# J2.net
KiCad netlist of a schematic drawn in Altium Designer
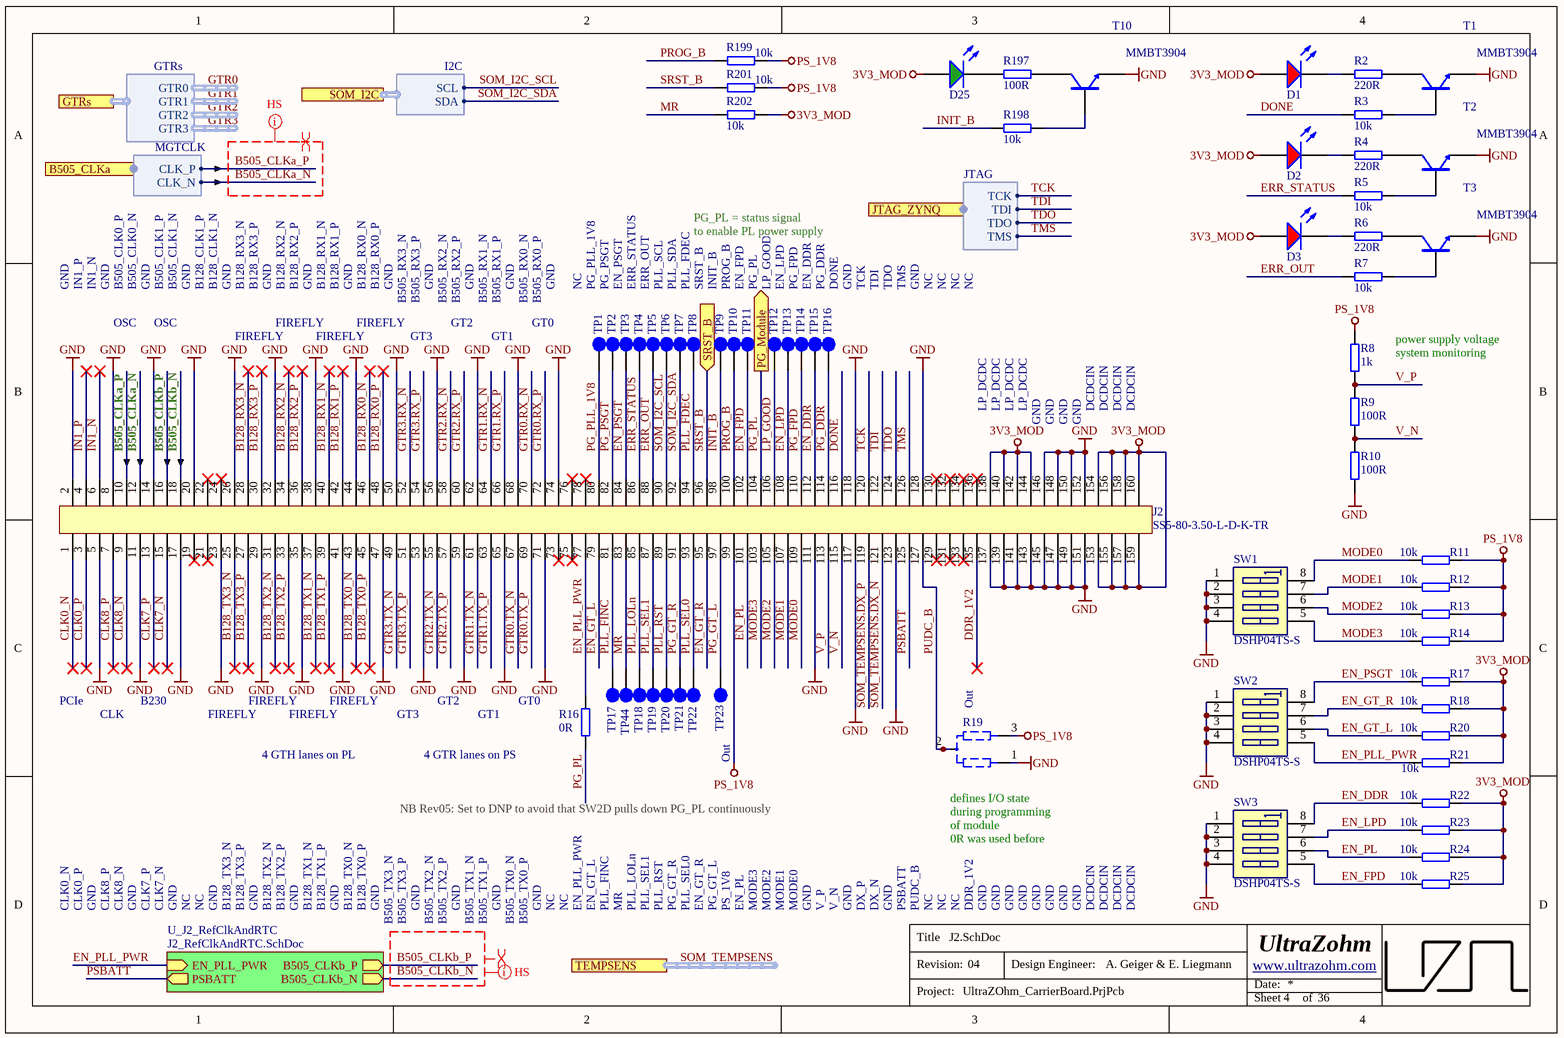
[diagram p0: J2.SchDoc]

(export (version "E")
  (design (tool "Eeschema 10.0.6"))
  (components
    (comp (ref "D1")
      (value "LED Red")
      (footprint "WL-SMCW_0603")
      (description "Standard LEDs - SMD 0603 red")
      (fields
        (field (name "MANUFACTURER PART NUMBER") "UZgen_LED_0603_Red")
        (field (name "MANUFACTURER") "UZgen")
        (field (name "CREATED FROM") "UZgenTool")
      )
      (libsource (lib "user") (part "LED_Red"))
    )
    (comp (ref "D2")
      (value "LED Red")
      (footprint "WL-SMCW_0603")
      (description "Standard LEDs - SMD 0603 red")
      (fields
        (field (name "MANUFACTURER PART NUMBER") "UZgen_LED_0603_Red")
        (field (name "MANUFACTURER") "UZgen")
        (field (name "CREATED FROM") "UZgenTool")
      )
      (libsource (lib "user") (part "LED_Red"))
    )
    (comp (ref "D3")
      (value "LED Red")
      (footprint "WL-SMCW_0603")
      (description "Standard LEDs - SMD 0603 red")
      (fields
        (field (name "MANUFACTURER PART NUMBER") "UZgen_LED_0603_Red")
        (field (name "MANUFACTURER") "UZgen")
        (field (name "CREATED FROM") "UZgenTool")
      )
      (libsource (lib "user") (part "LED_Red"))
    )
    (comp (ref "D25")
      (value "LED Green")
      (footprint "WL-SMCW_0603")
      (description "Standard LEDs - SMD 0603 green")
      (fields
        (field (name "MANUFACTURER PART NUMBER") "UZgen_LED_0603_Green")
        (field (name "MANUFACTURER") "UZgen")
        (field (name "CREATED FROM") "UZgenTool")
      )
      (libsource (lib "user") (part "LED_Green"))
    )
    (comp (ref "J2")
      (value "SS5-80-3.50-L-D-K-TR")
      (footprint "SS5-80-3.50-L-D-K-TR")
      (description "0.5 mm Ultra Fine Pitch Socket REF192552-01, 160 Pins")
      (fields
        (field (name "MANUFACTURER") "SAMTEC")
        (field (name "LCSC PART NUMBER") "C5292077")
        (field (name "CREATED FROM") "MGremer")
      )
      (libsource (lib "user") (part "SS5-80-3.50-L-D-K-TR"))
    )
    (comp (ref "R2")
      (value "220R")
      (footprint "R_0603_TE")
      (description "Generic resistor")
      (fields
        (field (name "TOLERANCE") "1 %")
        (field (name "MANUFACTURER PART NUMBER") "UZgen_R_0603_220R")
        (field (name "CREATED FROM") "UZgenTool")
      )
      (libsource (lib "user") (part "RES"))
    )
    (comp (ref "R3")
      (value "10k")
      (footprint "R_0603_TE")
      (description "Generic resistor")
      (fields
        (field (name "TOLERANCE") "1 %")
        (field (name "MANUFACTURER PART NUMBER") "UZgen_R_0603_10k")
        (field (name "CREATED FROM") "AGeiger")
      )
      (libsource (lib "user") (part "RES"))
    )
    (comp (ref "R4")
      (value "220R")
      (footprint "R_0603_TE")
      (description "Generic resistor")
      (fields
        (field (name "TOLERANCE") "1 %")
        (field (name "MANUFACTURER PART NUMBER") "UZgen_R_0603_220R")
        (field (name "CREATED FROM") "UZgenTool")
      )
      (libsource (lib "user") (part "RES"))
    )
    (comp (ref "R5")
      (value "10k")
      (footprint "R_0603_TE")
      (description "Generic resistor")
      (fields
        (field (name "TOLERANCE") "1 %")
        (field (name "MANUFACTURER PART NUMBER") "UZgen_R_0603_10k")
        (field (name "CREATED FROM") "AGeiger")
      )
      (libsource (lib "user") (part "RES"))
    )
    (comp (ref "R6")
      (value "220R")
      (footprint "R_0603_TE")
      (description "Generic resistor")
      (fields
        (field (name "TOLERANCE") "1 %")
        (field (name "MANUFACTURER PART NUMBER") "UZgen_R_0603_220R")
        (field (name "CREATED FROM") "UZgenTool")
      )
      (libsource (lib "user") (part "RES"))
    )
    (comp (ref "R7")
      (value "10k")
      (footprint "R_0603_TE")
      (description "Generic resistor")
      (fields
        (field (name "TOLERANCE") "1 %")
        (field (name "MANUFACTURER PART NUMBER") "UZgen_R_0603_10k")
        (field (name "CREATED FROM") "AGeiger")
      )
      (libsource (lib "user") (part "RES"))
    )
    (comp (ref "R8")
      (value "1k")
      (footprint "R_0603_TE")
      (description "Generic resistor")
      (fields
        (field (name "TOLERANCE") "1 %")
        (field (name "MANUFACTURER PART NUMBER") "UZgen_R_0603_1k")
        (field (name "CREATED FROM") "UZgenTool")
      )
      (libsource (lib "user") (part "RES"))
    )
    (comp (ref "R9")
      (value "100R")
      (footprint "R_0603_TE")
      (description "Generic resistor")
      (fields
        (field (name "TOLERANCE") "1 %")
        (field (name "MANUFACTURER PART NUMBER") "UZgen_R_0603_100R")
        (field (name "CREATED FROM") "UZgenTool")
      )
      (libsource (lib "user") (part "RES"))
    )
    (comp (ref "R10")
      (value "100R")
      (footprint "R_0603_TE")
      (description "Generic resistor")
      (fields
        (field (name "TOLERANCE") "1 %")
        (field (name "MANUFACTURER PART NUMBER") "UZgen_R_0603_100R")
        (field (name "CREATED FROM") "UZgenTool")
      )
      (libsource (lib "user") (part "RES"))
    )
    (comp (ref "R11")
      (value "10k")
      (footprint "R_0603_TE")
      (description "Generic resistor")
      (fields
        (field (name "TOLERANCE") "1 %")
        (field (name "MANUFACTURER PART NUMBER") "UZgen_R_0603_10k")
        (field (name "CREATED FROM") "AGeiger")
      )
      (libsource (lib "user") (part "RES"))
    )
    (comp (ref "R12")
      (value "10k")
      (footprint "R_0603_TE")
      (description "Generic resistor")
      (fields
        (field (name "TOLERANCE") "1 %")
        (field (name "MANUFACTURER PART NUMBER") "UZgen_R_0603_10k")
        (field (name "CREATED FROM") "AGeiger")
      )
      (libsource (lib "user") (part "RES"))
    )
    (comp (ref "R13")
      (value "10k")
      (footprint "R_0603_TE")
      (description "Generic resistor")
      (fields
        (field (name "TOLERANCE") "1 %")
        (field (name "MANUFACTURER PART NUMBER") "UZgen_R_0603_10k")
        (field (name "CREATED FROM") "AGeiger")
      )
      (libsource (lib "user") (part "RES"))
    )
    (comp (ref "R14")
      (value "10k")
      (footprint "R_0603_TE")
      (description "Generic resistor")
      (fields
        (field (name "TOLERANCE") "1 %")
        (field (name "MANUFACTURER PART NUMBER") "UZgen_R_0603_10k")
        (field (name "CREATED FROM") "AGeiger")
      )
      (libsource (lib "user") (part "RES"))
    )
    (comp (ref "R16")
      (value "0R")
      (footprint "R_0603_TE")
      (description "Generic resistor")
      (fields
        (field (name "TOLERANCE") "1 %")
        (field (name "MANUFACTURER PART NUMBER") "UZgen_R_0603_0R")
        (field (name "CREATED FROM") "UZgenTool")
      )
      (libsource (lib "user") (part "RES"))
    )
    (comp (ref "R17")
      (value "10k")
      (footprint "R_0603_TE")
      (description "Generic resistor")
      (fields
        (field (name "TOLERANCE") "1 %")
        (field (name "MANUFACTURER PART NUMBER") "UZgen_R_0603_10k")
        (field (name "CREATED FROM") "AGeiger")
      )
      (libsource (lib "user") (part "RES"))
    )
    (comp (ref "R18")
      (value "10k")
      (footprint "R_0603_TE")
      (description "Generic resistor")
      (fields
        (field (name "TOLERANCE") "1 %")
        (field (name "MANUFACTURER PART NUMBER") "UZgen_R_0603_10k")
        (field (name "CREATED FROM") "AGeiger")
      )
      (libsource (lib "user") (part "RES"))
    )
    (comp (ref "R19")
      (value "Manual Assembly 1608 (0603)")
      (footprint "TP_DUAL_RES_0603")
      (description "Manual Assembly Resistors Placeholder 1608 (0603) Dual")
      (libsource (lib "TE") (part "TP_DUAL_RES_0603"))
    )
    (comp (ref "R20")
      (value "10k")
      (footprint "R_0603_TE")
      (description "Generic resistor")
      (fields
        (field (name "TOLERANCE") "1 %")
        (field (name "MANUFACTURER PART NUMBER") "UZgen_R_0603_10k")
        (field (name "CREATED FROM") "AGeiger")
      )
      (libsource (lib "user") (part "RES"))
    )
    (comp (ref "R21")
      (value "10k")
      (footprint "R_0603_TE")
      (description "Generic resistor")
      (fields
        (field (name "TOLERANCE") "1 %")
        (field (name "MANUFACTURER PART NUMBER") "UZgen_R_0603_10k")
        (field (name "CREATED FROM") "AGeiger")
      )
      (libsource (lib "user") (part "RES"))
    )
    (comp (ref "R22")
      (value "10k")
      (footprint "R_0603_TE")
      (description "Generic resistor")
      (fields
        (field (name "TOLERANCE") "1 %")
        (field (name "MANUFACTURER PART NUMBER") "UZgen_R_0603_10k")
        (field (name "CREATED FROM") "AGeiger")
      )
      (libsource (lib "user") (part "RES"))
    )
    (comp (ref "R23")
      (value "10k")
      (footprint "R_0603_TE")
      (description "Generic resistor")
      (fields
        (field (name "TOLERANCE") "1 %")
        (field (name "MANUFACTURER PART NUMBER") "UZgen_R_0603_10k")
        (field (name "CREATED FROM") "AGeiger")
      )
      (libsource (lib "user") (part "RES"))
    )
    (comp (ref "R24")
      (value "10k")
      (footprint "R_0603_TE")
      (description "Generic resistor")
      (fields
        (field (name "TOLERANCE") "1 %")
        (field (name "MANUFACTURER PART NUMBER") "UZgen_R_0603_10k")
        (field (name "CREATED FROM") "AGeiger")
      )
      (libsource (lib "user") (part "RES"))
    )
    (comp (ref "R25")
      (value "10k")
      (footprint "R_0603_TE")
      (description "Generic resistor")
      (fields
        (field (name "TOLERANCE") "1 %")
        (field (name "MANUFACTURER PART NUMBER") "UZgen_R_0603_10k")
        (field (name "CREATED FROM") "AGeiger")
      )
      (libsource (lib "user") (part "RES"))
    )
    (comp (ref "R197")
      (value "100R")
      (footprint "R_0603_TE")
      (description "Generic resistor")
      (fields
        (field (name "TOLERANCE") "1 %")
        (field (name "MANUFACTURER PART NUMBER") "UZgen_R_0603_100R")
        (field (name "CREATED FROM") "UZgenTool")
      )
      (libsource (lib "user") (part "RES"))
    )
    (comp (ref "R198")
      (value "10k")
      (footprint "R_0603_TE")
      (description "Generic resistor")
      (fields
        (field (name "TOLERANCE") "1 %")
        (field (name "MANUFACTURER PART NUMBER") "UZgen_R_0603_10k")
        (field (name "CREATED FROM") "AGeiger")
      )
      (libsource (lib "user") (part "RES"))
    )
    (comp (ref "R199")
      (value "10k")
      (footprint "R_0603_TE")
      (description "Generic resistor")
      (fields
        (field (name "TOLERANCE") "1 %")
        (field (name "MANUFACTURER PART NUMBER") "UZgen_R_0603_10k")
        (field (name "CREATED FROM") "AGeiger")
      )
      (libsource (lib "user") (part "RES"))
    )
    (comp (ref "R201")
      (value "10k")
      (footprint "R_0603_TE")
      (description "Generic resistor")
      (fields
        (field (name "TOLERANCE") "1 %")
        (field (name "MANUFACTURER PART NUMBER") "UZgen_R_0603_10k")
        (field (name "CREATED FROM") "AGeiger")
      )
      (libsource (lib "user") (part "RES"))
    )
    (comp (ref "R202")
      (value "10k")
      (footprint "R_0603_TE")
      (description "Generic resistor")
      (fields
        (field (name "TOLERANCE") "1 %")
        (field (name "MANUFACTURER PART NUMBER") "UZgen_R_0603_10k")
        (field (name "CREATED FROM") "AGeiger")
      )
      (libsource (lib "user") (part "RES"))
    )
    (comp (ref "SW1")
      (value "DSHP04TS-S")
      (footprint "416131160804")
      (description "04p, 1.27mm Pitch, Horizontal, HP Type, SMT, flat Actuator, black, with Tape, T&R")
      (fields
        (field (name "MANUFACTURER") "XKB Connectivity")
        (field (name "LCSC PART NUMBER") "C319050")
        (field (name "CREATED FROM") "T. Wendt")
      )
      (libsource (lib "user") (part "DIP-SW-4p"))
    )
    (comp (ref "SW2")
      (value "DSHP04TS-S")
      (footprint "416131160804")
      (description "04p, 1.27mm Pitch, Horizontal, HP Type, SMT, flat Actuator, black, with Tape, T&R")
      (fields
        (field (name "MANUFACTURER") "XKB Connectivity")
        (field (name "LCSC PART NUMBER") "C319050")
        (field (name "CREATED FROM") "T. Wendt")
      )
      (libsource (lib "user") (part "DIP-SW-4p"))
    )
    (comp (ref "SW3")
      (value "DSHP04TS-S")
      (footprint "416131160804")
      (description "04p, 1.27mm Pitch, Horizontal, HP Type, SMT, flat Actuator, black, with Tape, T&R")
      (fields
        (field (name "MANUFACTURER") "XKB Connectivity")
        (field (name "LCSC PART NUMBER") "C319050")
        (field (name "CREATED FROM") "T. Wendt")
      )
      (libsource (lib "user") (part "DIP-SW-4p"))
    )
    (comp (ref "T1")
      (value "MMBT3904")
      (footprint "SOT95P280X145-3N")
      (fields
        (field (name "MANUFACTURER") "Jiangsu Changjing Electronics Technology Co., Ltd.")
        (field (name "LCSC PART NUMBER") "C20526")
        (field (name "CREATED FROM") "NDiringer")
      )
      (libsource (lib "user") (part "NPN-SOT23"))
    )
    (comp (ref "T2")
      (value "MMBT3904")
      (footprint "SOT95P280X145-3N")
      (fields
        (field (name "MANUFACTURER") "Jiangsu Changjing Electronics Technology Co., Ltd.")
        (field (name "LCSC PART NUMBER") "C20526")
        (field (name "CREATED FROM") "NDiringer")
      )
      (libsource (lib "user") (part "NPN-SOT23"))
    )
    (comp (ref "T3")
      (value "MMBT3904")
      (footprint "SOT95P280X145-3N")
      (fields
        (field (name "MANUFACTURER") "Jiangsu Changjing Electronics Technology Co., Ltd.")
        (field (name "LCSC PART NUMBER") "C20526")
        (field (name "CREATED FROM") "NDiringer")
      )
      (libsource (lib "user") (part "NPN-SOT23"))
    )
    (comp (ref "T10")
      (value "MMBT3904")
      (footprint "SOT95P280X145-3N")
      (fields
        (field (name "MANUFACTURER") "Jiangsu Changjing Electronics Technology Co., Ltd.")
        (field (name "LCSC PART NUMBER") "C20526")
        (field (name "CREATED FROM") "NDiringer")
      )
      (libsource (lib "user") (part "NPN-SOT23"))
    )
    (comp (ref "TP1") (value "Testpoint 1mm") (footprint "TP_1mm") (libsource (lib "TE") (part "TP")))
    (comp (ref "TP2") (value "Testpoint 1mm") (footprint "TP_1mm") (libsource (lib "TE") (part "TP")))
    (comp (ref "TP3") (value "Testpoint 1mm") (footprint "TP_1mm") (libsource (lib "TE") (part "TP")))
    (comp (ref "TP4") (value "Testpoint 1mm") (footprint "TP_1mm") (libsource (lib "TE") (part "TP")))
    (comp (ref "TP5") (value "Testpoint 1mm") (footprint "TP_1mm") (libsource (lib "TE") (part "TP")))
    (comp (ref "TP6") (value "Testpoint 1mm") (footprint "TP_1mm") (libsource (lib "TE") (part "TP")))
    (comp (ref "TP7") (value "Testpoint 1mm") (footprint "TP_1mm") (libsource (lib "TE") (part "TP")))
    (comp (ref "TP8") (value "Testpoint 1mm") (footprint "TP_1mm") (libsource (lib "TE") (part "TP")))
    (comp (ref "TP9") (value "Testpoint 1mm") (footprint "TP_1mm") (libsource (lib "TE") (part "TP")))
    (comp (ref "TP10") (value "Testpoint 1mm") (footprint "TP_1mm") (libsource (lib "TE") (part "TP")))
    (comp (ref "TP11") (value "Testpoint 1mm") (footprint "TP_1mm") (libsource (lib "TE") (part "TP")))
    (comp (ref "TP12") (value "Testpoint 1mm") (footprint "TP_1mm") (libsource (lib "TE") (part "TP")))
    (comp (ref "TP13") (value "Testpoint 1mm") (footprint "TP_1mm") (libsource (lib "TE") (part "TP")))
    (comp (ref "TP14") (value "Testpoint 1mm") (footprint "TP_1mm") (libsource (lib "TE") (part "TP")))
    (comp (ref "TP15") (value "Testpoint 1mm") (footprint "TP_1mm") (libsource (lib "TE") (part "TP")))
    (comp (ref "TP16") (value "Testpoint 1mm") (footprint "TP_1mm") (libsource (lib "TE") (part "TP")))
    (comp (ref "TP17") (value "Testpoint 1mm") (footprint "TP_1mm") (libsource (lib "TE") (part "TP")))
    (comp (ref "TP18") (value "Testpoint 1mm") (footprint "TP_1mm") (libsource (lib "TE") (part "TP")))
    (comp (ref "TP19") (value "Testpoint 1mm") (footprint "TP_1mm") (libsource (lib "TE") (part "TP")))
    (comp (ref "TP20") (value "Testpoint 1mm") (footprint "TP_1mm") (libsource (lib "TE") (part "TP")))
    (comp (ref "TP21") (value "Testpoint 1mm") (footprint "TP_1mm") (libsource (lib "TE") (part "TP")))
    (comp (ref "TP22") (value "Testpoint 1mm") (footprint "TP_1mm") (libsource (lib "TE") (part "TP")))
    (comp (ref "TP23") (value "Testpoint 1mm") (footprint "TP_1mm") (libsource (lib "TE") (part "TP")))
    (comp (ref "TP44") (value "Testpoint 1mm") (footprint "TP_1mm") (libsource (lib "TE") (part "TP")))
  )
  (nets
    (net (code "9") (name "/B128_RX0_N") (class "Default")
      (node (ref "J2") (pin "46") (pinfunction "46_46") (pintype "passive+no_connect"))
    )
    (net (code "10") (name "/B128_RX0_P") (class "Default")
      (node (ref "J2") (pin "48") (pinfunction "48_48") (pintype "passive+no_connect"))
    )
    (net (code "11") (name "/B128_RX1_N") (class "Default")
      (node (ref "J2") (pin "40") (pinfunction "40_40") (pintype "passive+no_connect"))
    )
    (net (code "12") (name "/B128_RX1_P") (class "Default")
      (node (ref "J2") (pin "42") (pinfunction "42_42") (pintype "passive+no_connect"))
    )
    (net (code "13") (name "/B128_RX2_N") (class "Default")
      (node (ref "J2") (pin "34") (pinfunction "34_34") (pintype "passive+no_connect"))
    )
    (net (code "14") (name "/B128_RX2_P") (class "Default")
      (node (ref "J2") (pin "36") (pinfunction "36_36") (pintype "passive+no_connect"))
    )
    (net (code "15") (name "/B128_RX3_N") (class "Default")
      (node (ref "J2") (pin "28") (pinfunction "28_28") (pintype "passive+no_connect"))
    )
    (net (code "16") (name "/B128_RX3_P") (class "Default")
      (node (ref "J2") (pin "30") (pinfunction "30_30") (pintype "passive+no_connect"))
    )
    (net (code "17") (name "/B128_TX0_N") (class "Default")
      (node (ref "J2") (pin "43") (pinfunction "43_43") (pintype "passive+no_connect"))
    )
    (net (code "18") (name "/B128_TX0_P") (class "Default")
      (node (ref "J2") (pin "45") (pinfunction "45_45") (pintype "passive+no_connect"))
    )
    (net (code "19") (name "/B128_TX1_N") (class "Default")
      (node (ref "J2") (pin "37") (pinfunction "37_37") (pintype "passive+no_connect"))
    )
    (net (code "20") (name "/B128_TX1_P") (class "Default")
      (node (ref "J2") (pin "39") (pinfunction "39_39") (pintype "passive+no_connect"))
    )
    (net (code "21") (name "/B128_TX2_N") (class "Default")
      (node (ref "J2") (pin "31") (pinfunction "31_31") (pintype "passive+no_connect"))
    )
    (net (code "22") (name "/B128_TX2_P") (class "Default")
      (node (ref "J2") (pin "33") (pinfunction "33_33") (pintype "passive+no_connect"))
    )
    (net (code "23") (name "/B128_TX3_N") (class "Default")
      (node (ref "J2") (pin "25") (pinfunction "25_25") (pintype "passive+no_connect"))
    )
    (net (code "24") (name "/B128_TX3_P") (class "Default")
      (node (ref "J2") (pin "27") (pinfunction "27_27") (pintype "passive+no_connect"))
    )
    (net (code "25") (name "/B505_CLKa_N") (class "Default")
      (node (ref "J2") (pin "12") (pinfunction "12_12") (pintype "passive"))
    )
    (net (code "26") (name "/B505_CLKa_P") (class "Default")
      (node (ref "J2") (pin "10") (pinfunction "10_10") (pintype "passive"))
    )
    (net (code "27") (name "/B505_CLKb_N") (class "Default")
      (node (ref "J2") (pin "18") (pinfunction "18_18") (pintype "passive"))
    )
    (net (code "28") (name "/B505_CLKb_P") (class "Default")
      (node (ref "J2") (pin "16") (pinfunction "16_16") (pintype "passive"))
    )
    (net (code "29") (name "/CLK0_N") (class "Default")
      (node (ref "J2") (pin "1") (pinfunction "1_1") (pintype "passive+no_connect"))
    )
    (net (code "30") (name "/CLK0_P") (class "Default")
      (node (ref "J2") (pin "3") (pinfunction "3_3") (pintype "passive+no_connect"))
    )
    (net (code "31") (name "/CLK7_N") (class "Default")
      (node (ref "J2") (pin "15") (pinfunction "15_15") (pintype "passive+no_connect"))
    )
    (net (code "32") (name "/CLK7_P") (class "Default")
      (node (ref "J2") (pin "13") (pinfunction "13_13") (pintype "passive+no_connect"))
    )
    (net (code "33") (name "/CLK8_N") (class "Default")
      (node (ref "J2") (pin "9") (pinfunction "9_9") (pintype "passive+no_connect"))
    )
    (net (code "34") (name "/CLK8_P") (class "Default")
      (node (ref "J2") (pin "7") (pinfunction "7_7") (pintype "passive+no_connect"))
    )
    (net (code "35") (name "/DDR_1V2") (class "Default")
      (node (ref "J2") (pin "135") (pinfunction "135_135") (pintype "passive+no_connect"))
    )
    (net (code "36") (name "/DONE") (class "Default")
      (node (ref "J2") (pin "116") (pinfunction "116_116") (pintype "passive"))
      (node (ref "R3") (pin "1") (pinfunction "1_1") (pintype "passive"))
    )
    (net (code "37") (name "/EN_DDR") (class "Default")
      (node (ref "J2") (pin "112") (pinfunction "112_112") (pintype "passive"))
      (node (ref "R22") (pin "1") (pinfunction "1_1") (pintype "passive"))
      (node (ref "SW3") (pin "8") (pinfunction "8_8") (pintype "passive"))
      (node (ref "TP15") (pin "1") (pintype "passive"))
    )
    (net (code "38") (name "/EN_FPD") (class "Default")
      (node (ref "J2") (pin "102") (pinfunction "102_102") (pintype "passive"))
      (node (ref "R25") (pin "1") (pinfunction "1_1") (pintype "passive"))
      (node (ref "SW3") (pin "5") (pinfunction "5_5") (pintype "passive"))
      (node (ref "TP11") (pin "1") (pintype "passive"))
    )
    (net (code "39") (name "/EN_GT_L") (class "Default")
      (node (ref "J2") (pin "79") (pinfunction "79_79") (pintype "passive"))
      (node (ref "R20") (pin "1") (pinfunction "1_1") (pintype "passive"))
      (node (ref "SW2") (pin "6") (pinfunction "6_6") (pintype "passive"))
    )
    (net (code "40") (name "/EN_GT_R") (class "Default")
      (node (ref "J2") (pin "95") (pinfunction "95_95") (pintype "passive"))
      (node (ref "R18") (pin "1") (pinfunction "1_1") (pintype "passive"))
      (node (ref "SW2") (pin "7") (pinfunction "7_7") (pintype "passive"))
    )
    (net (code "41") (name "/EN_LPD") (class "Default")
      (node (ref "J2") (pin "108") (pinfunction "108_108") (pintype "passive"))
      (node (ref "R23") (pin "1") (pinfunction "1_1") (pintype "passive"))
      (node (ref "SW3") (pin "7") (pinfunction "7_7") (pintype "passive"))
      (node (ref "TP13") (pin "1") (pintype "passive"))
    )
    (net (code "42") (name "/EN_PL") (class "Default")
      (node (ref "J2") (pin "101") (pinfunction "101_101") (pintype "passive"))
      (node (ref "R24") (pin "1") (pinfunction "1_1") (pintype "passive"))
      (node (ref "SW3") (pin "6") (pinfunction "6_6") (pintype "passive"))
    )
    (net (code "43") (name "/EN_PLL_PWR") (class "Default")
      (node (ref "J2") (pin "77") (pinfunction "77_77") (pintype "passive"))
      (node (ref "R16") (pin "2") (pinfunction "2_2") (pintype "passive"))
      (node (ref "R21") (pin "1") (pinfunction "1_1") (pintype "passive"))
      (node (ref "SW2") (pin "5") (pinfunction "5_5") (pintype "passive"))
    )
    (net (code "44") (name "/EN_PSGT") (class "Default")
      (node (ref "J2") (pin "84") (pinfunction "84_84") (pintype "passive"))
      (node (ref "R17") (pin "1") (pinfunction "1_1") (pintype "passive"))
      (node (ref "SW2") (pin "8") (pinfunction "8_8") (pintype "passive"))
      (node (ref "TP3") (pin "1") (pintype "passive"))
    )
    (net (code "45") (name "/ERR_OUT") (class "Default")
      (node (ref "J2") (pin "88") (pinfunction "88_88") (pintype "passive"))
      (node (ref "R7") (pin "1") (pinfunction "1_1") (pintype "passive"))
      (node (ref "TP5") (pin "1") (pintype "passive"))
    )
    (net (code "46") (name "/ERR_STATUS") (class "Default")
      (node (ref "J2") (pin "86") (pinfunction "86_86") (pintype "passive"))
      (node (ref "R5") (pin "1") (pinfunction "1_1") (pintype "passive"))
      (node (ref "TP4") (pin "1") (pintype "passive"))
    )
    (net (code "47") (name "/GTR0.RX_N") (class "Default")
      (node (ref "J2") (pin "70") (pinfunction "70_70") (pintype "passive"))
    )
    (net (code "48") (name "/GTR0.RX_P") (class "Default")
      (node (ref "J2") (pin "72") (pinfunction "72_72") (pintype "passive"))
    )
    (net (code "49") (name "/GTR0.TX_N") (class "Default")
      (node (ref "J2") (pin "67") (pinfunction "67_67") (pintype "passive"))
    )
    (net (code "50") (name "/GTR0.TX_P") (class "Default")
      (node (ref "J2") (pin "69") (pinfunction "69_69") (pintype "passive"))
    )
    (net (code "51") (name "/GTR1.RX_N") (class "Default")
      (node (ref "J2") (pin "64") (pinfunction "64_64") (pintype "passive"))
    )
    (net (code "52") (name "/GTR1.RX_P") (class "Default")
      (node (ref "J2") (pin "66") (pinfunction "66_66") (pintype "passive"))
    )
    (net (code "53") (name "/GTR1.TX_N") (class "Default")
      (node (ref "J2") (pin "61") (pinfunction "61_61") (pintype "passive"))
    )
    (net (code "54") (name "/GTR1.TX_P") (class "Default")
      (node (ref "J2") (pin "63") (pinfunction "63_63") (pintype "passive"))
    )
    (net (code "55") (name "/GTR2.RX_N") (class "Default")
      (node (ref "J2") (pin "58") (pinfunction "58_58") (pintype "passive"))
    )
    (net (code "56") (name "/GTR2.RX_P") (class "Default")
      (node (ref "J2") (pin "60") (pinfunction "60_60") (pintype "passive"))
    )
    (net (code "57") (name "/GTR2.TX_N") (class "Default")
      (node (ref "J2") (pin "55") (pinfunction "55_55") (pintype "passive"))
    )
    (net (code "58") (name "/GTR2.TX_P") (class "Default")
      (node (ref "J2") (pin "57") (pinfunction "57_57") (pintype "passive"))
    )
    (net (code "59") (name "/GTR3.RX_N") (class "Default")
      (node (ref "J2") (pin "52") (pinfunction "52_52") (pintype "passive"))
    )
    (net (code "60") (name "/GTR3.RX_P") (class "Default")
      (node (ref "J2") (pin "54") (pinfunction "54_54") (pintype "passive"))
    )
    (net (code "61") (name "/GTR3.TX_N") (class "Default")
      (node (ref "J2") (pin "49") (pinfunction "49_49") (pintype "passive"))
    )
    (net (code "62") (name "/GTR3.TX_P") (class "Default")
      (node (ref "J2") (pin "51") (pinfunction "51_51") (pintype "passive"))
    )
    (net (code "65") (name "/IN1_N") (class "Default")
      (node (ref "J2") (pin "6") (pinfunction "6_6") (pintype "passive+no_connect"))
    )
    (net (code "66") (name "/IN1_P") (class "Default")
      (node (ref "J2") (pin "4") (pinfunction "4_4") (pintype "passive+no_connect"))
    )
    (net (code "67") (name "/INIT_B") (class "Default")
      (node (ref "J2") (pin "98") (pinfunction "98_98") (pintype "passive"))
      (node (ref "R198") (pin "1") (pinfunction "1_1") (pintype "passive"))
      (node (ref "TP9") (pin "1") (pintype "passive"))
    )
    (net (code "68") (name "/LP_GOOD") (class "Default")
      (node (ref "J2") (pin "106") (pinfunction "106_106") (pintype "passive"))
      (node (ref "TP12") (pin "1") (pintype "passive"))
    )
    (net (code "69") (name "/MODE0") (class "Default")
      (node (ref "J2") (pin "109") (pinfunction "109_109") (pintype "passive"))
      (node (ref "R11") (pin "1") (pinfunction "1_1") (pintype "passive"))
      (node (ref "SW1") (pin "8") (pinfunction "8_8") (pintype "passive"))
    )
    (net (code "70") (name "/MODE1") (class "Default")
      (node (ref "J2") (pin "107") (pinfunction "107_107") (pintype "passive"))
      (node (ref "R12") (pin "1") (pinfunction "1_1") (pintype "passive"))
      (node (ref "SW1") (pin "7") (pinfunction "7_7") (pintype "passive"))
    )
    (net (code "71") (name "/MODE2") (class "Default")
      (node (ref "J2") (pin "105") (pinfunction "105_105") (pintype "passive"))
      (node (ref "R13") (pin "1") (pinfunction "1_1") (pintype "passive"))
      (node (ref "SW1") (pin "6") (pinfunction "6_6") (pintype "passive"))
    )
    (net (code "72") (name "/MODE3") (class "Default")
      (node (ref "J2") (pin "103") (pinfunction "103_103") (pintype "passive"))
      (node (ref "R14") (pin "1") (pinfunction "1_1") (pintype "passive"))
      (node (ref "SW1") (pin "5") (pinfunction "5_5") (pintype "passive"))
    )
    (net (code "73") (name "/MR") (class "Default")
      (node (ref "J2") (pin "83") (pinfunction "83_83") (pintype "passive"))
      (node (ref "R202") (pin "1") (pinfunction "1_1") (pintype "passive"))
      (node (ref "TP44") (pin "1") (pintype "passive"))
    )
    (net (code "74") (name "/PG_DDR") (class "Default")
      (node (ref "J2") (pin "114") (pinfunction "114_114") (pintype "passive"))
      (node (ref "TP16") (pin "1") (pintype "passive"))
    )
    (net (code "75") (name "/PG_FPD") (class "Default")
      (node (ref "J2") (pin "110") (pinfunction "110_110") (pintype "passive"))
      (node (ref "TP14") (pin "1") (pintype "passive"))
    )
    (net (code "76") (name "/PG_GT_L") (class "Default")
      (node (ref "J2") (pin "97") (pinfunction "97_97") (pintype "passive"))
      (node (ref "TP23") (pin "1") (pintype "passive"))
    )
    (net (code "77") (name "/PG_GT_R") (class "Default")
      (node (ref "J2") (pin "91") (pinfunction "91_91") (pintype "passive"))
      (node (ref "TP21") (pin "1") (pintype "passive"))
    )
    (net (code "78") (name "/PG_PL") (class "Default")
      (node (ref "J2") (pin "104") (pinfunction "104_104") (pintype "passive"))
      (node (ref "R16") (pin "1") (pinfunction "1_1") (pintype "passive"))
    )
    (net (code "79") (name "/PG_PLL_1V8") (class "Default")
      (node (ref "J2") (pin "80") (pinfunction "80_80") (pintype "passive"))
      (node (ref "TP1") (pin "1") (pintype "passive"))
    )
    (net (code "80") (name "/PG_PSGT") (class "Default")
      (node (ref "J2") (pin "82") (pinfunction "82_82") (pintype "passive"))
      (node (ref "TP2") (pin "1") (pintype "passive"))
    )
    (net (code "81") (name "/PLL_FDEC") (class "Default")
      (node (ref "J2") (pin "94") (pinfunction "94_94") (pintype "passive"))
      (node (ref "TP8") (pin "1") (pintype "passive"))
    )
    (net (code "82") (name "/PLL_FINC") (class "Default")
      (node (ref "J2") (pin "81") (pinfunction "81_81") (pintype "passive"))
      (node (ref "TP17") (pin "1") (pintype "passive"))
    )
    (net (code "83") (name "/PLL_LOLn") (class "Default")
      (node (ref "J2") (pin "85") (pinfunction "85_85") (pintype "passive"))
      (node (ref "TP18") (pin "1") (pintype "passive"))
    )
    (net (code "84") (name "/PLL_RST") (class "Default")
      (node (ref "J2") (pin "89") (pinfunction "89_89") (pintype "passive"))
      (node (ref "TP20") (pin "1") (pintype "passive"))
    )
    (net (code "85") (name "/PLL_SEL0") (class "Default")
      (node (ref "J2") (pin "93") (pinfunction "93_93") (pintype "passive"))
      (node (ref "TP22") (pin "1") (pintype "passive"))
    )
    (net (code "86") (name "/PLL_SEL1") (class "Default")
      (node (ref "J2") (pin "87") (pinfunction "87_87") (pintype "passive"))
      (node (ref "TP19") (pin "1") (pintype "passive"))
    )
    (net (code "87") (name "/PROG_B") (class "Default")
      (node (ref "J2") (pin "100") (pinfunction "100_100") (pintype "passive"))
      (node (ref "R199") (pin "1") (pinfunction "1_1") (pintype "passive"))
      (node (ref "TP10") (pin "1") (pintype "passive"))
    )
    (net (code "88") (name "/PSBATT") (class "Default")
      (node (ref "J2") (pin "125") (pinfunction "125_125") (pintype "passive"))
    )
    (net (code "89") (name "/PUDC_B") (class "Default")
      (node (ref "J2") (pin "127") (pinfunction "127_127") (pintype "passive"))
      (node (ref "R19") (pin "2") (pinfunction "2_2") (pintype "passive"))
    )
    (net (code "90") (name "/SOM_I2C_SCL") (class "Default")
      (node (ref "J2") (pin "90") (pinfunction "90_90") (pintype "passive"))
      (node (ref "TP6") (pin "1") (pintype "passive"))
    )
    (net (code "91") (name "/SOM_I2C_SDA") (class "Default")
      (node (ref "J2") (pin "92") (pinfunction "92_92") (pintype "passive"))
      (node (ref "TP7") (pin "1") (pintype "passive"))
    )
    (net (code "92") (name "/SOM_TEMPSENS.DX_N") (class "Default")
      (node (ref "J2") (pin "121") (pinfunction "121_121") (pintype "passive"))
    )
    (net (code "93") (name "/SOM_TEMPSENS.DX_P") (class "Default")
      (node (ref "J2") (pin "119") (pinfunction "119_119") (pintype "passive"))
    )
    (net (code "94") (name "/SRST_B") (class "Default")
      (node (ref "J2") (pin "96") (pinfunction "96_96") (pintype "passive"))
      (node (ref "R201") (pin "1") (pinfunction "1_1") (pintype "passive"))
    )
    (net (code "95") (name "/TCK") (class "Default")
      (node (ref "J2") (pin "120") (pinfunction "120_120") (pintype "passive"))
    )
    (net (code "96") (name "/TDI") (class "Default")
      (node (ref "J2") (pin "122") (pinfunction "122_122") (pintype "passive"))
    )
    (net (code "97") (name "/TDO") (class "Default")
      (node (ref "J2") (pin "124") (pinfunction "124_124") (pintype "passive"))
    )
    (net (code "98") (name "/TMS") (class "Default")
      (node (ref "J2") (pin "126") (pinfunction "126_126") (pintype "passive"))
    )
    (net (code "99") (name "/V_N") (class "Default")
      (node (ref "J2") (pin "115") (pinfunction "115_115") (pintype "passive"))
      (node (ref "R10") (pin "2") (pinfunction "2_2") (pintype "passive"))
      (node (ref "R9") (pin "1") (pinfunction "1_1") (pintype "passive"))
    )
    (net (code "100") (name "/V_P") (class "Default")
      (node (ref "J2") (pin "113") (pinfunction "113_113") (pintype "passive"))
      (node (ref "R8") (pin "1") (pinfunction "1_1") (pintype "passive"))
      (node (ref "R9") (pin "2") (pinfunction "2_2") (pintype "passive"))
    )
    (net (code "107") (name "3V3_MOD") (class "Default")
      (node (ref "D1") (pin "2") (pinfunction "A_2") (pintype "passive"))
      (node (ref "D2") (pin "2") (pinfunction "A_2") (pintype "passive"))
      (node (ref "D25") (pin "2") (pinfunction "A_2") (pintype "passive"))
      (node (ref "D3") (pin "2") (pinfunction "A_2") (pintype "passive"))
      (node (ref "J2") (pin "138") (pinfunction "138_138") (pintype "passive"))
      (node (ref "J2") (pin "140") (pinfunction "140_140") (pintype "passive"))
      (node (ref "J2") (pin "142") (pinfunction "142_142") (pintype "passive"))
      (node (ref "J2") (pin "144") (pinfunction "144_144") (pintype "passive"))
      (node (ref "J2") (pin "153") (pinfunction "153_153") (pintype "passive"))
      (node (ref "J2") (pin "154") (pinfunction "154_154") (pintype "passive"))
      (node (ref "J2") (pin "155") (pinfunction "155_155") (pintype "passive"))
      (node (ref "J2") (pin "156") (pinfunction "156_156") (pintype "passive"))
      (node (ref "J2") (pin "157") (pinfunction "157_157") (pintype "passive"))
      (node (ref "J2") (pin "158") (pinfunction "158_158") (pintype "passive"))
      (node (ref "J2") (pin "159") (pinfunction "159_159") (pintype "passive"))
      (node (ref "J2") (pin "160") (pinfunction "160_160") (pintype "passive"))
      (node (ref "R17") (pin "2") (pinfunction "2_2") (pintype "passive"))
      (node (ref "R18") (pin "2") (pinfunction "2_2") (pintype "passive"))
      (node (ref "R20") (pin "2") (pinfunction "2_2") (pintype "passive"))
      (node (ref "R202") (pin "2") (pinfunction "2_2") (pintype "passive"))
      (node (ref "R21") (pin "2") (pinfunction "2_2") (pintype "passive"))
      (node (ref "R22") (pin "2") (pinfunction "2_2") (pintype "passive"))
      (node (ref "R23") (pin "2") (pinfunction "2_2") (pintype "passive"))
      (node (ref "R24") (pin "2") (pinfunction "2_2") (pintype "passive"))
      (node (ref "R25") (pin "2") (pinfunction "2_2") (pintype "passive"))
    )
    (net (code "108") (name "GND") (class "Default")
      (node (ref "J2") (pin "11") (pinfunction "11_11") (pintype "passive"))
      (node (ref "J2") (pin "111") (pinfunction "111_111") (pintype "passive"))
      (node (ref "J2") (pin "117") (pinfunction "117_117") (pintype "passive"))
      (node (ref "J2") (pin "118") (pinfunction "118_118") (pintype "passive"))
      (node (ref "J2") (pin "123") (pinfunction "123_123") (pintype "passive"))
      (node (ref "J2") (pin "128") (pinfunction "128_128") (pintype "passive"))
      (node (ref "J2") (pin "137") (pinfunction "137_137") (pintype "passive"))
      (node (ref "J2") (pin "139") (pinfunction "139_139") (pintype "passive"))
      (node (ref "J2") (pin "14") (pinfunction "14_14") (pintype "passive"))
      (node (ref "J2") (pin "141") (pinfunction "141_141") (pintype "passive"))
      (node (ref "J2") (pin "143") (pinfunction "143_143") (pintype "passive"))
      (node (ref "J2") (pin "145") (pinfunction "145_145") (pintype "passive"))
      (node (ref "J2") (pin "146") (pinfunction "146_146") (pintype "passive"))
      (node (ref "J2") (pin "147") (pinfunction "147_147") (pintype "passive"))
      (node (ref "J2") (pin "148") (pinfunction "148_148") (pintype "passive"))
      (node (ref "J2") (pin "149") (pinfunction "149_149") (pintype "passive"))
      (node (ref "J2") (pin "150") (pinfunction "150_150") (pintype "passive"))
      (node (ref "J2") (pin "151") (pinfunction "151_151") (pintype "passive"))
      (node (ref "J2") (pin "152") (pinfunction "152_152") (pintype "passive"))
      (node (ref "J2") (pin "17") (pinfunction "17_17") (pintype "passive"))
      (node (ref "J2") (pin "2") (pinfunction "2_2") (pintype "passive"))
      (node (ref "J2") (pin "20") (pinfunction "20_20") (pintype "passive"))
      (node (ref "J2") (pin "23") (pinfunction "23_23") (pintype "passive"))
      (node (ref "J2") (pin "26") (pinfunction "26_26") (pintype "passive"))
      (node (ref "J2") (pin "29") (pinfunction "29_29") (pintype "passive"))
      (node (ref "J2") (pin "32") (pinfunction "32_32") (pintype "passive"))
      (node (ref "J2") (pin "35") (pinfunction "35_35") (pintype "passive"))
      (node (ref "J2") (pin "38") (pinfunction "38_38") (pintype "passive"))
      (node (ref "J2") (pin "41") (pinfunction "41_41") (pintype "passive"))
      (node (ref "J2") (pin "44") (pinfunction "44_44") (pintype "passive"))
      (node (ref "J2") (pin "47") (pinfunction "47_47") (pintype "passive"))
      (node (ref "J2") (pin "5") (pinfunction "5_5") (pintype "passive"))
      (node (ref "J2") (pin "50") (pinfunction "50_50") (pintype "passive"))
      (node (ref "J2") (pin "53") (pinfunction "53_53") (pintype "passive"))
      (node (ref "J2") (pin "56") (pinfunction "56_56") (pintype "passive"))
      (node (ref "J2") (pin "59") (pinfunction "59_59") (pintype "passive"))
      (node (ref "J2") (pin "62") (pinfunction "62_62") (pintype "passive"))
      (node (ref "J2") (pin "65") (pinfunction "65_65") (pintype "passive"))
      (node (ref "J2") (pin "68") (pinfunction "68_68") (pintype "passive"))
      (node (ref "J2") (pin "71") (pinfunction "71_71") (pintype "passive"))
      (node (ref "J2") (pin "74") (pinfunction "74_74") (pintype "passive"))
      (node (ref "J2") (pin "8") (pinfunction "8_8") (pintype "passive"))
      (node (ref "R10") (pin "1") (pinfunction "1_1") (pintype "passive"))
      (node (ref "R19") (pin "1") (pinfunction "1_1") (pintype "passive"))
      (node (ref "SW1") (pin "1") (pinfunction "1_1") (pintype "passive"))
      (node (ref "SW1") (pin "2") (pinfunction "2_2") (pintype "passive"))
      (node (ref "SW1") (pin "3") (pinfunction "3_3") (pintype "passive"))
      (node (ref "SW1") (pin "4") (pinfunction "4_4") (pintype "passive"))
      (node (ref "SW2") (pin "1") (pinfunction "1_1") (pintype "passive"))
      (node (ref "SW2") (pin "2") (pinfunction "2_2") (pintype "passive"))
      (node (ref "SW2") (pin "3") (pinfunction "3_3") (pintype "passive"))
      (node (ref "SW2") (pin "4") (pinfunction "4_4") (pintype "passive"))
      (node (ref "SW3") (pin "1") (pinfunction "1_1") (pintype "passive"))
      (node (ref "SW3") (pin "2") (pinfunction "2_2") (pintype "passive"))
      (node (ref "SW3") (pin "3") (pinfunction "3_3") (pintype "passive"))
      (node (ref "SW3") (pin "4") (pinfunction "4_4") (pintype "passive"))
      (node (ref "T1") (pin "2") (pinfunction "EMITTER_2") (pintype "passive"))
      (node (ref "T10") (pin "2") (pinfunction "EMITTER_2") (pintype "passive"))
      (node (ref "T2") (pin "2") (pinfunction "EMITTER_2") (pintype "passive"))
      (node (ref "T3") (pin "2") (pinfunction "EMITTER_2") (pintype "passive"))
    )
    (net (code "109") (name "Net-(D1-K)") (class "Default")
      (node (ref "D1") (pin "1") (pinfunction "K_1") (pintype "passive"))
      (node (ref "R2") (pin "1") (pinfunction "1_1") (pintype "passive"))
    )
    (net (code "110") (name "Net-(D2-K)") (class "Default")
      (node (ref "D2") (pin "1") (pinfunction "K_1") (pintype "passive"))
      (node (ref "R4") (pin "1") (pinfunction "1_1") (pintype "passive"))
    )
    (net (code "111") (name "Net-(D3-K)") (class "Default")
      (node (ref "D3") (pin "1") (pinfunction "K_1") (pintype "passive"))
      (node (ref "R6") (pin "1") (pinfunction "1_1") (pintype "passive"))
    )
    (net (code "112") (name "Net-(D25-K)") (class "Default")
      (node (ref "D25") (pin "1") (pinfunction "K_1") (pintype "passive"))
      (node (ref "R197") (pin "2") (pinfunction "2_2") (pintype "passive"))
    )
    (net (code "113") (name "Net-(T1-BASIS)") (class "Default")
      (node (ref "R3") (pin "2") (pinfunction "2_2") (pintype "passive"))
      (node (ref "T1") (pin "1") (pinfunction "BASIS_1") (pintype "passive"))
    )
    (net (code "114") (name "Net-(T1-COLLECTOR)") (class "Default")
      (node (ref "R2") (pin "2") (pinfunction "2_2") (pintype "passive"))
      (node (ref "T1") (pin "3") (pinfunction "COLLECTOR_3") (pintype "passive"))
    )
    (net (code "115") (name "Net-(T2-BASIS)") (class "Default")
      (node (ref "R5") (pin "2") (pinfunction "2_2") (pintype "passive"))
      (node (ref "T2") (pin "1") (pinfunction "BASIS_1") (pintype "passive"))
    )
    (net (code "116") (name "Net-(T2-COLLECTOR)") (class "Default")
      (node (ref "R4") (pin "2") (pinfunction "2_2") (pintype "passive"))
      (node (ref "T2") (pin "3") (pinfunction "COLLECTOR_3") (pintype "passive"))
    )
    (net (code "117") (name "Net-(T3-BASIS)") (class "Default")
      (node (ref "R7") (pin "2") (pinfunction "2_2") (pintype "passive"))
      (node (ref "T3") (pin "1") (pinfunction "BASIS_1") (pintype "passive"))
    )
    (net (code "118") (name "Net-(T3-COLLECTOR)") (class "Default")
      (node (ref "R6") (pin "2") (pinfunction "2_2") (pintype "passive"))
      (node (ref "T3") (pin "3") (pinfunction "COLLECTOR_3") (pintype "passive"))
    )
    (net (code "119") (name "Net-(T10-BASIS)") (class "Default")
      (node (ref "R198") (pin "2") (pinfunction "2_2") (pintype "passive"))
      (node (ref "T10") (pin "1") (pinfunction "BASIS_1") (pintype "passive"))
    )
    (net (code "120") (name "Net-(T10-COLLECTOR)") (class "Default")
      (node (ref "R197") (pin "1") (pinfunction "1_1") (pintype "passive"))
      (node (ref "T10") (pin "3") (pinfunction "COLLECTOR_3") (pintype "passive"))
    )
    (net (code "121") (name "PS_1V8") (class "Default")
      (node (ref "J2") (pin "99") (pinfunction "99_99") (pintype "passive"))
      (node (ref "R11") (pin "2") (pinfunction "2_2") (pintype "passive"))
      (node (ref "R12") (pin "2") (pinfunction "2_2") (pintype "passive"))
      (node (ref "R13") (pin "2") (pinfunction "2_2") (pintype "passive"))
      (node (ref "R14") (pin "2") (pinfunction "2_2") (pintype "passive"))
      (node (ref "R19") (pin "3") (pinfunction "3_3") (pintype "passive"))
      (node (ref "R199") (pin "2") (pinfunction "2_2") (pintype "passive"))
      (node (ref "R201") (pin "2") (pinfunction "2_2") (pintype "passive"))
      (node (ref "R8") (pin "2") (pinfunction "2_2") (pintype "passive"))
    )
    (net (code "122") (name "unconnected-(J2-Pad19)") (class "Default")
      (node (ref "J2") (pin "19") (pinfunction "19_19") (pintype "passive+no_connect"))
    )
    (net (code "123") (name "unconnected-(J2-Pad21)") (class "Default")
      (node (ref "J2") (pin "21") (pinfunction "21_21") (pintype "passive+no_connect"))
    )
    (net (code "124") (name "unconnected-(J2-Pad22)") (class "Default")
      (node (ref "J2") (pin "22") (pinfunction "22_22") (pintype "passive+no_connect"))
    )
    (net (code "125") (name "unconnected-(J2-Pad24)") (class "Default")
      (node (ref "J2") (pin "24") (pinfunction "24_24") (pintype "passive+no_connect"))
    )
    (net (code "126") (name "unconnected-(J2-Pad73)") (class "Default")
      (node (ref "J2") (pin "73") (pinfunction "73_73") (pintype "passive+no_connect"))
    )
    (net (code "127") (name "unconnected-(J2-Pad75)") (class "Default")
      (node (ref "J2") (pin "75") (pinfunction "75_75") (pintype "passive+no_connect"))
    )
    (net (code "128") (name "unconnected-(J2-Pad76)") (class "Default")
      (node (ref "J2") (pin "76") (pinfunction "76_76") (pintype "passive+no_connect"))
    )
    (net (code "129") (name "unconnected-(J2-Pad78)") (class "Default")
      (node (ref "J2") (pin "78") (pinfunction "78_78") (pintype "passive+no_connect"))
    )
    (net (code "130") (name "unconnected-(J2-Pad129)") (class "Default")
      (node (ref "J2") (pin "129") (pinfunction "129_129") (pintype "passive+no_connect"))
    )
    (net (code "131") (name "unconnected-(J2-Pad130)") (class "Default")
      (node (ref "J2") (pin "130") (pinfunction "130_130") (pintype "passive+no_connect"))
    )
    (net (code "132") (name "unconnected-(J2-Pad131)") (class "Default")
      (node (ref "J2") (pin "131") (pinfunction "131_131") (pintype "passive+no_connect"))
    )
    (net (code "133") (name "unconnected-(J2-Pad132)") (class "Default")
      (node (ref "J2") (pin "132") (pinfunction "132_132") (pintype "passive+no_connect"))
    )
    (net (code "134") (name "unconnected-(J2-Pad133)") (class "Default")
      (node (ref "J2") (pin "133") (pinfunction "133_133") (pintype "passive+no_connect"))
    )
    (net (code "135") (name "unconnected-(J2-Pad134)") (class "Default")
      (node (ref "J2") (pin "134") (pinfunction "134_134") (pintype "passive+no_connect"))
    )
    (net (code "136") (name "unconnected-(J2-Pad136)") (class "Default")
      (node (ref "J2") (pin "136") (pinfunction "136_136") (pintype "passive+no_connect"))
    )
  )
)
